# Elvis_PCI.net
KiCad netlist of a schematic drawn in Altium Designer
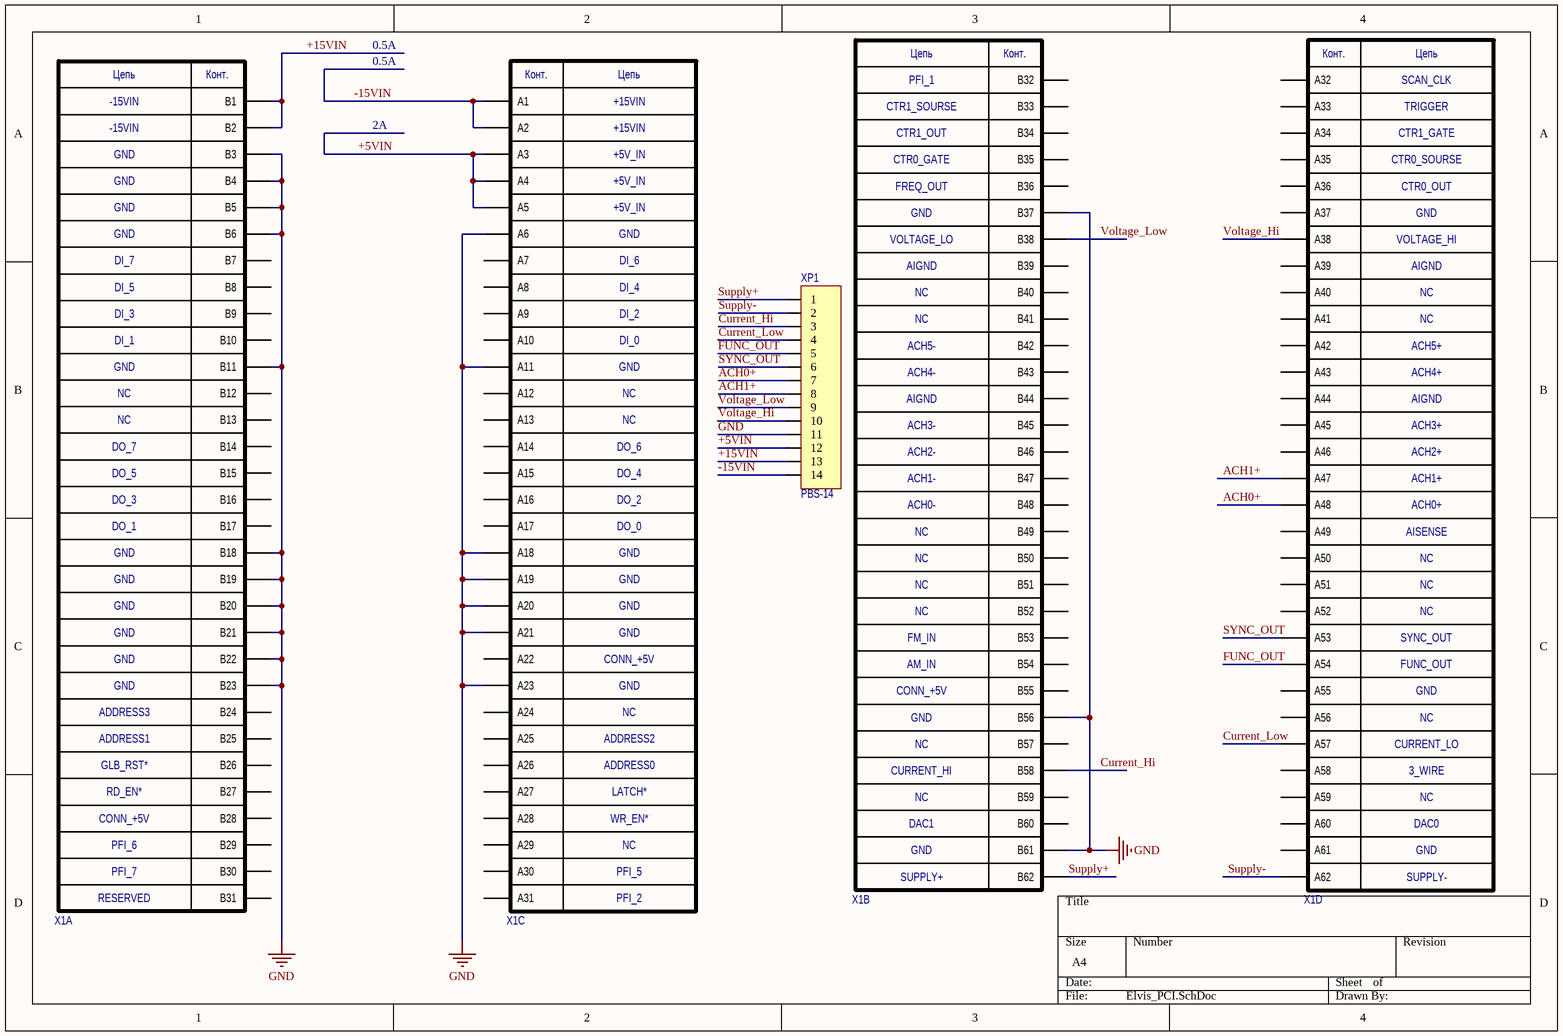
[diagram p0: Elvis_PCI.SchDoc]

(export (version "E")
  (design (tool "Eeschema 10.0.6"))
  (components
    (comp (ref "X1") (value "PCI") (footprint "PCI") (libsource (lib "my_AP_lib_sch") (part "PCI")))
    (comp (ref "XP1") (value "PBS-14") (footprint "PBS-14") (libsource (lib "my_AP_lib_sch") (part "PBS-14")))
  )
  (nets
    (net (code "1") (name "/+5VIN") (class "Default")
      (node (ref "X1") (pin "A3") (pinfunction "A3_A3") (pintype "passive"))
      (node (ref "X1") (pin "A4") (pinfunction "A4_A4") (pintype "passive"))
      (node (ref "X1") (pin "A5") (pinfunction "A5_A5") (pintype "passive"))
      (node (ref "XP1") (pin "12") (pinfunction "12_12") (pintype "passive"))
    )
    (net (code "2") (name "/+15VIN") (class "Default")
      (node (ref "X1") (pin "B1") (pinfunction "B1_B1") (pintype "passive"))
      (node (ref "X1") (pin "B2") (pinfunction "B2_B2") (pintype "passive"))
      (node (ref "XP1") (pin "13") (pinfunction "13_13") (pintype "passive"))
    )
    (net (code "3") (name "/-15VIN") (class "Default")
      (node (ref "X1") (pin "A1") (pinfunction "A1_A1") (pintype "passive"))
      (node (ref "X1") (pin "A2") (pinfunction "A2_A2") (pintype "passive"))
      (node (ref "XP1") (pin "14") (pinfunction "14_14") (pintype "passive"))
    )
    (net (code "4") (name "/ACH0+") (class "Default")
      (node (ref "X1") (pin "A48") (pinfunction "A48_A48") (pintype "passive"))
      (node (ref "XP1") (pin "7") (pinfunction "7_7") (pintype "passive"))
    )
    (net (code "5") (name "/ACH1+") (class "Default")
      (node (ref "X1") (pin "A47") (pinfunction "A47_A47") (pintype "passive"))
      (node (ref "XP1") (pin "8") (pinfunction "8_8") (pintype "passive"))
    )
    (net (code "6") (name "/Current_Hi") (class "Default")
      (node (ref "X1") (pin "B58") (pinfunction "B58_B58") (pintype "passive"))
      (node (ref "XP1") (pin "3") (pinfunction "3_3") (pintype "passive"))
    )
    (net (code "7") (name "/Current_Low") (class "Default")
      (node (ref "X1") (pin "A57") (pinfunction "A57_A57") (pintype "passive"))
      (node (ref "XP1") (pin "4") (pinfunction "4_4") (pintype "passive"))
    )
    (net (code "8") (name "/FUNC_OUT") (class "Default")
      (node (ref "X1") (pin "A54") (pinfunction "A54_A54") (pintype "passive"))
      (node (ref "XP1") (pin "5") (pinfunction "5_5") (pintype "passive"))
    )
    (net (code "9") (name "/SYNC_OUT") (class "Default")
      (node (ref "X1") (pin "A53") (pinfunction "A53_A53") (pintype "passive"))
      (node (ref "XP1") (pin "6") (pinfunction "6_6") (pintype "passive"))
    )
    (net (code "10") (name "/Supply+") (class "Default")
      (node (ref "X1") (pin "B62") (pinfunction "B62_B62") (pintype "passive"))
      (node (ref "XP1") (pin "1") (pinfunction "1_1") (pintype "passive"))
    )
    (net (code "11") (name "/Supply-") (class "Default")
      (node (ref "X1") (pin "A62") (pinfunction "A62_A62") (pintype "passive"))
      (node (ref "XP1") (pin "2") (pinfunction "2_2") (pintype "passive"))
    )
    (net (code "12") (name "/Voltage_Hi") (class "Default")
      (node (ref "X1") (pin "A38") (pinfunction "A38_A38") (pintype "passive"))
      (node (ref "XP1") (pin "10") (pinfunction "10_10") (pintype "passive"))
    )
    (net (code "13") (name "/Voltage_Low") (class "Default")
      (node (ref "X1") (pin "B38") (pinfunction "B38_B38") (pintype "passive"))
      (node (ref "XP1") (pin "9") (pinfunction "9_9") (pintype "passive"))
    )
    (net (code "14") (name "GND") (class "Default")
      (node (ref "X1") (pin "A11") (pinfunction "A11_A11") (pintype "passive"))
      (node (ref "X1") (pin "A18") (pinfunction "A18_A18") (pintype "passive"))
      (node (ref "X1") (pin "A19") (pinfunction "A19_A19") (pintype "passive"))
      (node (ref "X1") (pin "A20") (pinfunction "A20_A20") (pintype "passive"))
      (node (ref "X1") (pin "A21") (pinfunction "A21_A21") (pintype "passive"))
      (node (ref "X1") (pin "A23") (pinfunction "A23_A23") (pintype "passive"))
      (node (ref "X1") (pin "A6") (pinfunction "A6_A6") (pintype "passive"))
      (node (ref "X1") (pin "B11") (pinfunction "B11_B11") (pintype "passive"))
      (node (ref "X1") (pin "B18") (pinfunction "B18_B18") (pintype "passive"))
      (node (ref "X1") (pin "B19") (pinfunction "B19_B19") (pintype "passive"))
      (node (ref "X1") (pin "B20") (pinfunction "B20_B20") (pintype "passive"))
      (node (ref "X1") (pin "B21") (pinfunction "B21_B21") (pintype "passive"))
      (node (ref "X1") (pin "B22") (pinfunction "B22_B22") (pintype "passive"))
      (node (ref "X1") (pin "B23") (pinfunction "B23_B23") (pintype "passive"))
      (node (ref "X1") (pin "B3") (pinfunction "B3_B3") (pintype "passive"))
      (node (ref "X1") (pin "B37") (pinfunction "B37_B37") (pintype "passive"))
      (node (ref "X1") (pin "B4") (pinfunction "B4_B4") (pintype "passive"))
      (node (ref "X1") (pin "B5") (pinfunction "B5_B5") (pintype "passive"))
      (node (ref "X1") (pin "B56") (pinfunction "B56_B56") (pintype "passive"))
      (node (ref "X1") (pin "B6") (pinfunction "B6_B6") (pintype "passive"))
      (node (ref "X1") (pin "B61") (pinfunction "B61_B61") (pintype "passive"))
      (node (ref "XP1") (pin "11") (pinfunction "11_11") (pintype "passive"))
    )
    (net (code "15") (name "unconnected-(X1-PadA7)") (class "Default")
      (node (ref "X1") (pin "A7") (pinfunction "A7_A7") (pintype "passive"))
    )
    (net (code "16") (name "unconnected-(X1-PadA8)") (class "Default")
      (node (ref "X1") (pin "A8") (pinfunction "A8_A8") (pintype "passive"))
    )
    (net (code "17") (name "unconnected-(X1-PadA9)") (class "Default")
      (node (ref "X1") (pin "A9") (pinfunction "A9_A9") (pintype "passive"))
    )
    (net (code "18") (name "unconnected-(X1-PadA10)") (class "Default")
      (node (ref "X1") (pin "A10") (pinfunction "A10_A10") (pintype "passive"))
    )
    (net (code "19") (name "unconnected-(X1-PadA12)") (class "Default")
      (node (ref "X1") (pin "A12") (pinfunction "A12_A12") (pintype "passive"))
    )
    (net (code "20") (name "unconnected-(X1-PadA13)") (class "Default")
      (node (ref "X1") (pin "A13") (pinfunction "A13_A13") (pintype "passive"))
    )
    (net (code "21") (name "unconnected-(X1-PadA14)") (class "Default")
      (node (ref "X1") (pin "A14") (pinfunction "A14_A14") (pintype "passive"))
    )
    (net (code "22") (name "unconnected-(X1-PadA15)") (class "Default")
      (node (ref "X1") (pin "A15") (pinfunction "A15_A15") (pintype "passive"))
    )
    (net (code "23") (name "unconnected-(X1-PadA16)") (class "Default")
      (node (ref "X1") (pin "A16") (pinfunction "A16_A16") (pintype "passive"))
    )
    (net (code "24") (name "unconnected-(X1-PadA17)") (class "Default")
      (node (ref "X1") (pin "A17") (pinfunction "A17_A17") (pintype "passive"))
    )
    (net (code "25") (name "unconnected-(X1-PadA22)") (class "Default")
      (node (ref "X1") (pin "A22") (pinfunction "A22_A22") (pintype "passive"))
    )
    (net (code "26") (name "unconnected-(X1-PadA24)") (class "Default")
      (node (ref "X1") (pin "A24") (pinfunction "A24_A24") (pintype "passive"))
    )
    (net (code "27") (name "unconnected-(X1-PadA25)") (class "Default")
      (node (ref "X1") (pin "A25") (pinfunction "A25_A25") (pintype "passive"))
    )
    (net (code "28") (name "unconnected-(X1-PadA26)") (class "Default")
      (node (ref "X1") (pin "A26") (pinfunction "A26_A26") (pintype "passive"))
    )
    (net (code "29") (name "unconnected-(X1-PadA27)") (class "Default")
      (node (ref "X1") (pin "A27") (pinfunction "A27_A27") (pintype "passive"))
    )
    (net (code "30") (name "unconnected-(X1-PadA28)") (class "Default")
      (node (ref "X1") (pin "A28") (pinfunction "A28_A28") (pintype "passive"))
    )
    (net (code "31") (name "unconnected-(X1-PadA29)") (class "Default")
      (node (ref "X1") (pin "A29") (pinfunction "A29_A29") (pintype "passive"))
    )
    (net (code "32") (name "unconnected-(X1-PadA30)") (class "Default")
      (node (ref "X1") (pin "A30") (pinfunction "A30_A30") (pintype "passive"))
    )
    (net (code "33") (name "unconnected-(X1-PadA31)") (class "Default")
      (node (ref "X1") (pin "A31") (pinfunction "A31_A31") (pintype "passive"))
    )
    (net (code "34") (name "unconnected-(X1-PadA32)") (class "Default")
      (node (ref "X1") (pin "A32") (pinfunction "A32_A32") (pintype "passive"))
    )
    (net (code "35") (name "unconnected-(X1-PadA33)") (class "Default")
      (node (ref "X1") (pin "A33") (pinfunction "A33_A33") (pintype "passive"))
    )
    (net (code "36") (name "unconnected-(X1-PadA34)") (class "Default")
      (node (ref "X1") (pin "A34") (pinfunction "A34_A34") (pintype "passive"))
    )
    (net (code "37") (name "unconnected-(X1-PadA35)") (class "Default")
      (node (ref "X1") (pin "A35") (pinfunction "A35_A35") (pintype "passive"))
    )
    (net (code "38") (name "unconnected-(X1-PadA36)") (class "Default")
      (node (ref "X1") (pin "A36") (pinfunction "A36_A36") (pintype "passive"))
    )
    (net (code "39") (name "unconnected-(X1-PadA37)") (class "Default")
      (node (ref "X1") (pin "A37") (pinfunction "A37_A37") (pintype "passive"))
    )
    (net (code "40") (name "unconnected-(X1-PadA39)") (class "Default")
      (node (ref "X1") (pin "A39") (pinfunction "A39_A39") (pintype "passive"))
    )
    (net (code "41") (name "unconnected-(X1-PadA40)") (class "Default")
      (node (ref "X1") (pin "A40") (pinfunction "A40_A40") (pintype "passive"))
    )
    (net (code "42") (name "unconnected-(X1-PadA41)") (class "Default")
      (node (ref "X1") (pin "A41") (pinfunction "A41_A41") (pintype "passive"))
    )
    (net (code "43") (name "unconnected-(X1-PadA42)") (class "Default")
      (node (ref "X1") (pin "A42") (pinfunction "A42_A42") (pintype "passive"))
    )
    (net (code "44") (name "unconnected-(X1-PadA43)") (class "Default")
      (node (ref "X1") (pin "A43") (pinfunction "A43_A43") (pintype "passive"))
    )
    (net (code "45") (name "unconnected-(X1-PadA44)") (class "Default")
      (node (ref "X1") (pin "A44") (pinfunction "A44_A44") (pintype "passive"))
    )
    (net (code "46") (name "unconnected-(X1-PadA45)") (class "Default")
      (node (ref "X1") (pin "A45") (pinfunction "A45_A45") (pintype "passive"))
    )
    (net (code "47") (name "unconnected-(X1-PadA46)") (class "Default")
      (node (ref "X1") (pin "A46") (pinfunction "A46_A46") (pintype "passive"))
    )
    (net (code "48") (name "unconnected-(X1-PadA49)") (class "Default")
      (node (ref "X1") (pin "A49") (pinfunction "A49_A49") (pintype "passive"))
    )
    (net (code "49") (name "unconnected-(X1-PadA50)") (class "Default")
      (node (ref "X1") (pin "A50") (pinfunction "A50_A50") (pintype "passive"))
    )
    (net (code "50") (name "unconnected-(X1-PadA51)") (class "Default")
      (node (ref "X1") (pin "A51") (pinfunction "A51_A51") (pintype "passive"))
    )
    (net (code "51") (name "unconnected-(X1-PadA52)") (class "Default")
      (node (ref "X1") (pin "A52") (pinfunction "A52_A52") (pintype "passive"))
    )
    (net (code "52") (name "unconnected-(X1-PadA55)") (class "Default")
      (node (ref "X1") (pin "A55") (pinfunction "A55_A55") (pintype "passive"))
    )
    (net (code "53") (name "unconnected-(X1-PadA56)") (class "Default")
      (node (ref "X1") (pin "A56") (pinfunction "A56_A56") (pintype "passive"))
    )
    (net (code "54") (name "unconnected-(X1-PadA58)") (class "Default")
      (node (ref "X1") (pin "A58") (pinfunction "A58_A58") (pintype "passive"))
    )
    (net (code "55") (name "unconnected-(X1-PadA59)") (class "Default")
      (node (ref "X1") (pin "A59") (pinfunction "A59_A59") (pintype "passive"))
    )
    (net (code "56") (name "unconnected-(X1-PadA60)") (class "Default")
      (node (ref "X1") (pin "A60") (pinfunction "A60_A60") (pintype "passive"))
    )
    (net (code "57") (name "unconnected-(X1-PadA61)") (class "Default")
      (node (ref "X1") (pin "A61") (pinfunction "A61_A61") (pintype "passive"))
    )
    (net (code "58") (name "unconnected-(X1-PadB7)") (class "Default")
      (node (ref "X1") (pin "B7") (pinfunction "B7_B7") (pintype "passive"))
    )
    (net (code "59") (name "unconnected-(X1-PadB8)") (class "Default")
      (node (ref "X1") (pin "B8") (pinfunction "B8_B8") (pintype "passive"))
    )
    (net (code "60") (name "unconnected-(X1-PadB9)") (class "Default")
      (node (ref "X1") (pin "B9") (pinfunction "B9_B9") (pintype "passive"))
    )
    (net (code "61") (name "unconnected-(X1-PadB10)") (class "Default")
      (node (ref "X1") (pin "B10") (pinfunction "B10_B10") (pintype "passive"))
    )
    (net (code "62") (name "unconnected-(X1-PadB12)") (class "Default")
      (node (ref "X1") (pin "B12") (pinfunction "B12_B12") (pintype "passive"))
    )
    (net (code "63") (name "unconnected-(X1-PadB13)") (class "Default")
      (node (ref "X1") (pin "B13") (pinfunction "B13_B13") (pintype "passive"))
    )
    (net (code "64") (name "unconnected-(X1-PadB14)") (class "Default")
      (node (ref "X1") (pin "B14") (pinfunction "B14_B14") (pintype "passive"))
    )
    (net (code "65") (name "unconnected-(X1-PadB15)") (class "Default")
      (node (ref "X1") (pin "B15") (pinfunction "B15_B15") (pintype "passive"))
    )
    (net (code "66") (name "unconnected-(X1-PadB16)") (class "Default")
      (node (ref "X1") (pin "B16") (pinfunction "B16_B16") (pintype "passive"))
    )
    (net (code "67") (name "unconnected-(X1-PadB17)") (class "Default")
      (node (ref "X1") (pin "B17") (pinfunction "B17_B17") (pintype "passive"))
    )
    (net (code "68") (name "unconnected-(X1-PadB24)") (class "Default")
      (node (ref "X1") (pin "B24") (pinfunction "B24_B24") (pintype "passive"))
    )
    (net (code "69") (name "unconnected-(X1-PadB25)") (class "Default")
      (node (ref "X1") (pin "B25") (pinfunction "B25_B25") (pintype "passive"))
    )
    (net (code "70") (name "unconnected-(X1-PadB26)") (class "Default")
      (node (ref "X1") (pin "B26") (pinfunction "B26_B26") (pintype "passive"))
    )
    (net (code "71") (name "unconnected-(X1-PadB27)") (class "Default")
      (node (ref "X1") (pin "B27") (pinfunction "B27_B27") (pintype "passive"))
    )
    (net (code "72") (name "unconnected-(X1-PadB28)") (class "Default")
      (node (ref "X1") (pin "B28") (pinfunction "B28_B28") (pintype "passive"))
    )
    (net (code "73") (name "unconnected-(X1-PadB29)") (class "Default")
      (node (ref "X1") (pin "B29") (pinfunction "B29_B29") (pintype "passive"))
    )
    (net (code "74") (name "unconnected-(X1-PadB30)") (class "Default")
      (node (ref "X1") (pin "B30") (pinfunction "B30_B30") (pintype "passive"))
    )
    (net (code "75") (name "unconnected-(X1-PadB31)") (class "Default")
      (node (ref "X1") (pin "B31") (pinfunction "B31_B31") (pintype "passive"))
    )
    (net (code "76") (name "unconnected-(X1-PadB32)") (class "Default")
      (node (ref "X1") (pin "B32") (pinfunction "B32_B32") (pintype "passive"))
    )
    (net (code "77") (name "unconnected-(X1-PadB33)") (class "Default")
      (node (ref "X1") (pin "B33") (pinfunction "B33_B33") (pintype "passive"))
    )
    (net (code "78") (name "unconnected-(X1-PadB34)") (class "Default")
      (node (ref "X1") (pin "B34") (pinfunction "B34_B34") (pintype "passive"))
    )
    (net (code "79") (name "unconnected-(X1-PadB35)") (class "Default")
      (node (ref "X1") (pin "B35") (pinfunction "B35_B35") (pintype "passive"))
    )
    (net (code "80") (name "unconnected-(X1-PadB36)") (class "Default")
      (node (ref "X1") (pin "B36") (pinfunction "B36_B36") (pintype "passive"))
    )
    (net (code "81") (name "unconnected-(X1-PadB39)") (class "Default")
      (node (ref "X1") (pin "B39") (pinfunction "B39_B39") (pintype "passive"))
    )
    (net (code "82") (name "unconnected-(X1-PadB40)") (class "Default")
      (node (ref "X1") (pin "B40") (pinfunction "B40_B40") (pintype "passive"))
    )
    (net (code "83") (name "unconnected-(X1-PadB41)") (class "Default")
      (node (ref "X1") (pin "B41") (pinfunction "B41_B41") (pintype "passive"))
    )
    (net (code "84") (name "unconnected-(X1-PadB42)") (class "Default")
      (node (ref "X1") (pin "B42") (pinfunction "B42_B42") (pintype "passive"))
    )
    (net (code "85") (name "unconnected-(X1-PadB43)") (class "Default")
      (node (ref "X1") (pin "B43") (pinfunction "B43_B43") (pintype "passive"))
    )
    (net (code "86") (name "unconnected-(X1-PadB44)") (class "Default")
      (node (ref "X1") (pin "B44") (pinfunction "B44_B44") (pintype "passive"))
    )
    (net (code "87") (name "unconnected-(X1-PadB45)") (class "Default")
      (node (ref "X1") (pin "B45") (pinfunction "B45_B45") (pintype "passive"))
    )
    (net (code "88") (name "unconnected-(X1-PadB46)") (class "Default")
      (node (ref "X1") (pin "B46") (pinfunction "B46_B46") (pintype "passive"))
    )
    (net (code "89") (name "unconnected-(X1-PadB47)") (class "Default")
      (node (ref "X1") (pin "B47") (pinfunction "B47_B47") (pintype "passive"))
    )
    (net (code "90") (name "unconnected-(X1-PadB48)") (class "Default")
      (node (ref "X1") (pin "B48") (pinfunction "B48_B48") (pintype "passive"))
    )
    (net (code "91") (name "unconnected-(X1-PadB49)") (class "Default")
      (node (ref "X1") (pin "B49") (pinfunction "B49_B49") (pintype "passive"))
    )
    (net (code "92") (name "unconnected-(X1-PadB50)") (class "Default")
      (node (ref "X1") (pin "B50") (pinfunction "B50_B50") (pintype "passive"))
    )
    (net (code "93") (name "unconnected-(X1-PadB51)") (class "Default")
      (node (ref "X1") (pin "B51") (pinfunction "B51_B51") (pintype "passive"))
    )
    (net (code "94") (name "unconnected-(X1-PadB52)") (class "Default")
      (node (ref "X1") (pin "B52") (pinfunction "B52_B52") (pintype "passive"))
    )
    (net (code "95") (name "unconnected-(X1-PadB53)") (class "Default")
      (node (ref "X1") (pin "B53") (pinfunction "B53_B53") (pintype "passive"))
    )
    (net (code "96") (name "unconnected-(X1-PadB54)") (class "Default")
      (node (ref "X1") (pin "B54") (pinfunction "B54_B54") (pintype "passive"))
    )
    (net (code "97") (name "unconnected-(X1-PadB55)") (class "Default")
      (node (ref "X1") (pin "B55") (pinfunction "B55_B55") (pintype "passive"))
    )
    (net (code "98") (name "unconnected-(X1-PadB57)") (class "Default")
      (node (ref "X1") (pin "B57") (pinfunction "B57_B57") (pintype "passive"))
    )
    (net (code "99") (name "unconnected-(X1-PadB59)") (class "Default")
      (node (ref "X1") (pin "B59") (pinfunction "B59_B59") (pintype "passive"))
    )
    (net (code "100") (name "unconnected-(X1-PadB60)") (class "Default")
      (node (ref "X1") (pin "B60") (pinfunction "B60_B60") (pintype "passive"))
    )
  )
)
